# openHCOP-micro.net
KiCad netlist of a schematic drawn in EAGLE
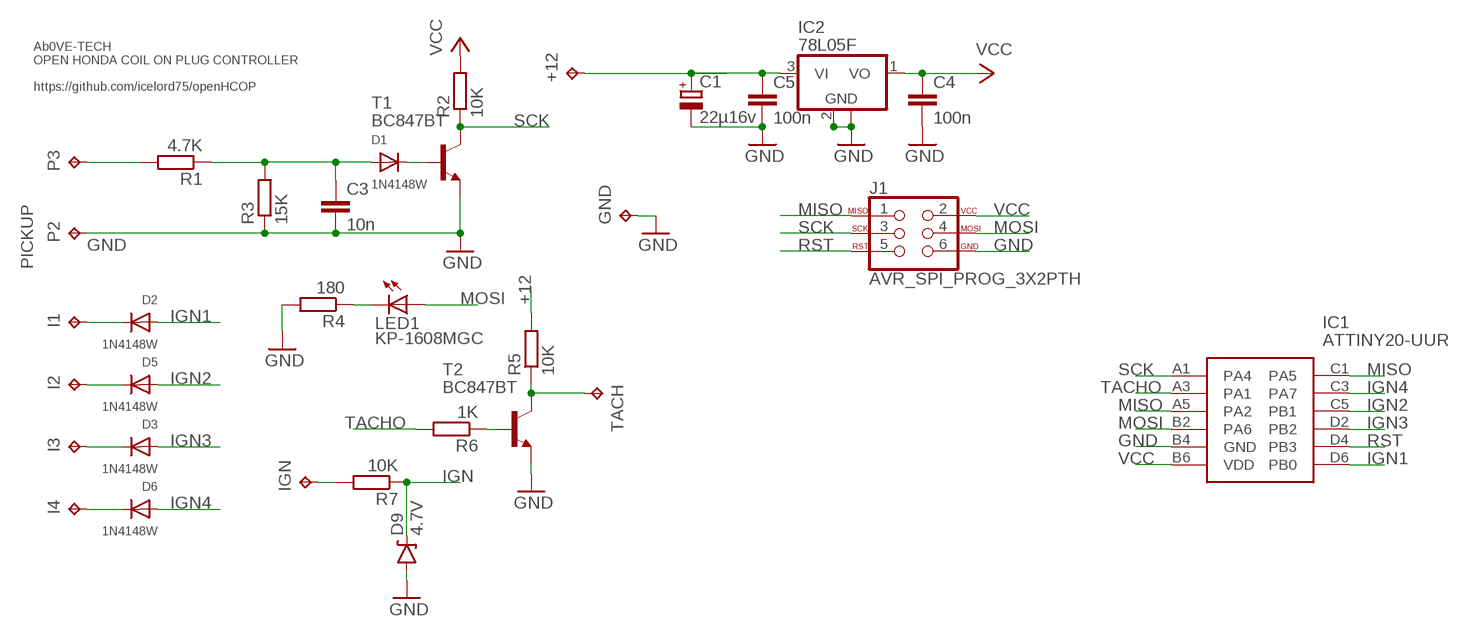
[diagram p0: schematic, sheet 1]

(export (version "E")
  (design (tool "Eeschema 10.0.6"))
  (components
    (comp (ref "+12")
      (value "TPPAD1-13Y")
      (footprint "eagle-import:P1-13Y")
      (libsource (lib "eagle-import") (part "TPPAD1-13Y"))
    )
    (comp (ref "C1")
      (value "22µ16v")
      (footprint "eagle-import:SMC_B")
      (libsource (lib "eagle-import") (part "CPOL-EUSMCB"))
    )
    (comp (ref "C3")
      (value "10n")
      (footprint "eagle-import:C0402")
      (libsource (lib "eagle-import") (part "C-EUC0402"))
    )
    (comp (ref "C4")
      (value "100n")
      (footprint "eagle-import:C0402")
      (libsource (lib "eagle-import") (part "C-EUC0402"))
    )
    (comp (ref "C5")
      (value "100n")
      (footprint "eagle-import:C0402")
      (libsource (lib "eagle-import") (part "C-EUC0402"))
    )
    (comp (ref "D1")
      (value "1N4148W")
      (footprint "eagle-import:SOD882(T)")
      (libsource (lib "eagle-import") (part "BAS16L"))
    )
    (comp (ref "D2")
      (value "1N4148W")
      (footprint "eagle-import:SOD882(T)")
      (libsource (lib "eagle-import") (part "BAS16L"))
    )
    (comp (ref "D3")
      (value "1N4148W")
      (footprint "eagle-import:SOD882(T)")
      (libsource (lib "eagle-import") (part "BAS16L"))
    )
    (comp (ref "D5")
      (value "1N4148W")
      (footprint "eagle-import:SOD882(T)")
      (libsource (lib "eagle-import") (part "BAS16L"))
    )
    (comp (ref "D6")
      (value "1N4148W")
      (footprint "eagle-import:SOD882(T)")
      (libsource (lib "eagle-import") (part "BAS16L"))
    )
    (comp (ref "D9")
      (value "4.7V")
      (footprint "eagle-import:SOD-123")
      (libsource (lib "eagle-import") (part "DIODE-ZENER16V"))
    )
    (comp (ref "GND")
      (value "TPPAD1-13Y")
      (footprint "eagle-import:P1-13Y")
      (libsource (lib "eagle-import") (part "TPPAD1-13Y"))
    )
    (comp (ref "I1")
      (value "TPPAD1-13Y")
      (footprint "eagle-import:P1-13Y")
      (libsource (lib "eagle-import") (part "TPPAD1-13Y"))
    )
    (comp (ref "I2")
      (value "TPPAD1-13Y")
      (footprint "eagle-import:P1-13Y")
      (libsource (lib "eagle-import") (part "TPPAD1-13Y"))
    )
    (comp (ref "I3")
      (value "TPPAD1-13Y")
      (footprint "eagle-import:P1-13Y")
      (libsource (lib "eagle-import") (part "TPPAD1-13Y"))
    )
    (comp (ref "I4")
      (value "TPPAD1-13Y")
      (footprint "eagle-import:P1-13Y")
      (libsource (lib "eagle-import") (part "TPPAD1-13Y"))
    )
    (comp (ref "IC1")
      (value "ATTINY20-UUR")
      (footprint "eagle-import:BGA12C40P6X4_156X140X54")
      (fields (field (name "MOUSER_PART_NUMBER") "556-ATTINY20-UUR"))
      (libsource (lib "eagle-import") (part "ATTINY20-UUR"))
    )
    (comp (ref "IC2")
      (value "78L05F")
      (footprint "eagle-import:SOT89")
      (libsource (lib "eagle-import") (part "78LF05"))
    )
    (comp (ref "IGN")
      (value "TPPAD1-13Y")
      (footprint "eagle-import:P1-13Y")
      (libsource (lib "eagle-import") (part "TPPAD1-13Y"))
    )
    (comp (ref "J1")
      (value "AVR_SPI_PROG_3X2PTH")
      (footprint "eagle-import:2X3")
      (libsource (lib "eagle-import") (part "AVR_SPI_PROG_3X2PTH"))
    )
    (comp (ref "LED1")
      (value "KP-1608MGC")
      (footprint "eagle-import:CHIPLED_0603")
      (libsource (lib "eagle-import") (part "LEDCHIPLED_0603"))
    )
    (comp (ref "P2")
      (value "TPPAD1-13Y")
      (footprint "eagle-import:P1-13Y")
      (libsource (lib "eagle-import") (part "TPPAD1-13Y"))
    )
    (comp (ref "P3")
      (value "TPPAD1-13Y")
      (footprint "eagle-import:P1-13Y")
      (libsource (lib "eagle-import") (part "TPPAD1-13Y"))
    )
    (comp (ref "R1")
      (value "4.7K")
      (footprint "eagle-import:R0402")
      (libsource (lib "eagle-import") (part "R-EU_R0402"))
    )
    (comp (ref "R2")
      (value "10K")
      (footprint "eagle-import:R0402")
      (libsource (lib "eagle-import") (part "R-EU_R0402"))
    )
    (comp (ref "R3")
      (value "15K")
      (footprint "eagle-import:R0402")
      (libsource (lib "eagle-import") (part "R-EU_R0402"))
    )
    (comp (ref "R4")
      (value "180")
      (footprint "eagle-import:R0402")
      (libsource (lib "eagle-import") (part "R-EU_R0402"))
    )
    (comp (ref "R5")
      (value "10K")
      (footprint "eagle-import:R0402")
      (libsource (lib "eagle-import") (part "R-EU_R0402"))
    )
    (comp (ref "R6")
      (value "1K")
      (footprint "eagle-import:R0402")
      (libsource (lib "eagle-import") (part "R-EU_R0402"))
    )
    (comp (ref "R7")
      (value "10K")
      (footprint "eagle-import:R0402")
      (libsource (lib "eagle-import") (part "R-EU_R0402"))
    )
    (comp (ref "T1")
      (value "BC847BT")
      (footprint "eagle-import:SOT416")
      (libsource (lib "eagle-import") (part "BC847TB"))
    )
    (comp (ref "T2")
      (value "BC847BT")
      (footprint "eagle-import:SOT416")
      (libsource (lib "eagle-import") (part "BC847TB"))
    )
    (comp (ref "TACH")
      (value "TPPAD1-13Y")
      (footprint "eagle-import:P1-13Y")
      (libsource (lib "eagle-import") (part "TPPAD1-13Y"))
    )
  )
  (nets
    (net (code "1") (name "/+12") (class "Default")
      (node (ref "+12") (pin "TP") (pinfunction "TP_TP") (pintype "input"))
      (node (ref "C1") (pin "+") (pinfunction "+_+") (pintype "passive"))
      (node (ref "C5") (pin "1") (pinfunction "1_1") (pintype "passive"))
      (node (ref "IC2") (pin "3") (pinfunction "VI_3") (pintype "input"))
      (node (ref "R5") (pin "2") (pinfunction "2_2") (pintype "passive"))
    )
    (net (code "2") (name "/IGN") (class "Default")
      (node (ref "D9") (pin "C") (pinfunction "C_C") (pintype "passive"))
      (node (ref "R7") (pin "1") (pinfunction "1_1") (pintype "passive"))
    )
    (net (code "3") (name "/IGN1") (class "Default")
      (node (ref "D2") (pin "2") (pinfunction "A_2") (pintype "passive"))
      (node (ref "IC1") (pin "D6") (pinfunction "PB0_D6") (pintype "bidirectional"))
    )
    (net (code "4") (name "/IGN2") (class "Default")
      (node (ref "D5") (pin "2") (pinfunction "A_2") (pintype "passive"))
      (node (ref "IC1") (pin "C5") (pinfunction "PB1_C5") (pintype "bidirectional"))
    )
    (net (code "5") (name "/IGN3") (class "Default")
      (node (ref "D3") (pin "2") (pinfunction "A_2") (pintype "passive"))
      (node (ref "IC1") (pin "D2") (pinfunction "PB2_D2") (pintype "bidirectional"))
    )
    (net (code "6") (name "/IGN4") (class "Default")
      (node (ref "D6") (pin "2") (pinfunction "A_2") (pintype "passive"))
      (node (ref "IC1") (pin "C3") (pinfunction "PA7_C3") (pintype "bidirectional"))
    )
    (net (code "7") (name "/MISO") (class "Default")
      (node (ref "IC1") (pin "A5") (pinfunction "PA2_A5") (pintype "bidirectional"))
      (node (ref "IC1") (pin "C1") (pinfunction "PA5_C1") (pintype "bidirectional"))
      (node (ref "J1") (pin "1") (pinfunction "1_1") (pintype "passive"))
    )
    (net (code "8") (name "/MOSI") (class "Default")
      (node (ref "IC1") (pin "B2") (pinfunction "PA6_B2") (pintype "bidirectional"))
      (node (ref "J1") (pin "4") (pinfunction "4_4") (pintype "passive"))
      (node (ref "LED1") (pin "A") (pinfunction "A_A") (pintype "passive"))
    )
    (net (code "9") (name "/PICKUP") (class "Default")
      (node (ref "P3") (pin "TP") (pinfunction "TP_TP") (pintype "input"))
      (node (ref "R1") (pin "2") (pinfunction "2_2") (pintype "passive"))
    )
    (net (code "10") (name "/RST") (class "Default")
      (node (ref "IC1") (pin "D4") (pinfunction "PB3_D4") (pintype "bidirectional"))
      (node (ref "J1") (pin "5") (pinfunction "5_5") (pintype "passive"))
    )
    (net (code "11") (name "/SCK") (class "Default")
      (node (ref "IC1") (pin "A1") (pinfunction "PA4_A1") (pintype "bidirectional"))
      (node (ref "J1") (pin "3") (pinfunction "3_3") (pintype "passive"))
      (node (ref "R2") (pin "1") (pinfunction "1_1") (pintype "passive"))
      (node (ref "T1") (pin "3") (pinfunction "C_3") (pintype "passive"))
    )
    (net (code "12") (name "/TACHO") (class "Default")
      (node (ref "IC1") (pin "A3") (pinfunction "PA1_A3") (pintype "bidirectional"))
      (node (ref "R6") (pin "2") (pinfunction "2_2") (pintype "passive"))
    )
    (net (code "13") (name "GND") (class "Default")
      (node (ref "C1") (pin "-") (pinfunction "-_-") (pintype "passive"))
      (node (ref "C3") (pin "2") (pinfunction "2_2") (pintype "passive"))
      (node (ref "C4") (pin "2") (pinfunction "2_2") (pintype "passive"))
      (node (ref "C5") (pin "2") (pinfunction "2_2") (pintype "passive"))
      (node (ref "D9") (pin "A") (pinfunction "A_A") (pintype "passive"))
      (node (ref "GND") (pin "TP") (pinfunction "TP_TP") (pintype "input"))
      (node (ref "IC1") (pin "B4") (pinfunction "GND_B4") (pintype "bidirectional"))
      (node (ref "IC2") (pin "2") (pinfunction "GND_2") (pintype "passive"))
      (node (ref "IC2") (pin "2@1") (pinfunction "GND_2@1") (pintype "passive"))
      (node (ref "J1") (pin "6") (pinfunction "6_6") (pintype "passive"))
      (node (ref "P2") (pin "TP") (pinfunction "TP_TP") (pintype "input"))
      (node (ref "R3") (pin "1") (pinfunction "1_1") (pintype "passive"))
      (node (ref "R4") (pin "2") (pinfunction "2_2") (pintype "passive"))
      (node (ref "T1") (pin "2") (pinfunction "E_2") (pintype "passive"))
      (node (ref "T2") (pin "2") (pinfunction "E_2") (pintype "passive"))
    )
    (net (code "14") (name "Net-(D1-A)") (class "Default")
      (node (ref "C3") (pin "1") (pinfunction "1_1") (pintype "passive"))
      (node (ref "D1") (pin "2") (pinfunction "A_2") (pintype "passive"))
      (node (ref "R1") (pin "1") (pinfunction "1_1") (pintype "passive"))
      (node (ref "R3") (pin "2") (pinfunction "2_2") (pintype "passive"))
    )
    (net (code "15") (name "Net-(D1-K)") (class "Default")
      (node (ref "D1") (pin "1") (pinfunction "K_1") (pintype "passive"))
      (node (ref "T1") (pin "1") (pinfunction "B_1") (pintype "passive"))
    )
    (net (code "16") (name "Net-(D2-K)") (class "Default")
      (node (ref "D2") (pin "1") (pinfunction "K_1") (pintype "passive"))
      (node (ref "I1") (pin "TP") (pinfunction "TP_TP") (pintype "input"))
    )
    (net (code "17") (name "Net-(D3-K)") (class "Default")
      (node (ref "D3") (pin "1") (pinfunction "K_1") (pintype "passive"))
      (node (ref "I3") (pin "TP") (pinfunction "TP_TP") (pintype "input"))
    )
    (net (code "18") (name "Net-(D5-K)") (class "Default")
      (node (ref "D5") (pin "1") (pinfunction "K_1") (pintype "passive"))
      (node (ref "I2") (pin "TP") (pinfunction "TP_TP") (pintype "input"))
    )
    (net (code "19") (name "Net-(D6-K)") (class "Default")
      (node (ref "D6") (pin "1") (pinfunction "K_1") (pintype "passive"))
      (node (ref "I4") (pin "TP") (pinfunction "TP_TP") (pintype "input"))
    )
    (net (code "20") (name "Net-(IGN-PadTP)") (class "Default")
      (node (ref "IGN") (pin "TP") (pinfunction "TP_TP") (pintype "input"))
      (node (ref "R7") (pin "2") (pinfunction "2_2") (pintype "passive"))
    )
    (net (code "21") (name "Net-(LED1-PadC)") (class "Default")
      (node (ref "LED1") (pin "C") (pinfunction "C_C") (pintype "passive"))
      (node (ref "R4") (pin "1") (pinfunction "1_1") (pintype "passive"))
    )
    (net (code "22") (name "Net-(T2-B)") (class "Default")
      (node (ref "R6") (pin "1") (pinfunction "1_1") (pintype "passive"))
      (node (ref "T2") (pin "1") (pinfunction "B_1") (pintype "passive"))
    )
    (net (code "23") (name "Net-(T2-C)") (class "Default")
      (node (ref "R5") (pin "1") (pinfunction "1_1") (pintype "passive"))
      (node (ref "T2") (pin "3") (pinfunction "C_3") (pintype "passive"))
      (node (ref "TACH") (pin "TP") (pinfunction "TP_TP") (pintype "input"))
    )
    (net (code "24") (name "VCC") (class "Default")
      (node (ref "C4") (pin "1") (pinfunction "1_1") (pintype "passive"))
      (node (ref "IC1") (pin "B6") (pinfunction "VDD_B6") (pintype "bidirectional"))
      (node (ref "IC2") (pin "1") (pinfunction "VO_1") (pintype "passive"))
      (node (ref "J1") (pin "2") (pinfunction "2_2") (pintype "passive"))
      (node (ref "R2") (pin "2") (pinfunction "2_2") (pintype "passive"))
    )
  )
)
